# IMU.net
KiCad netlist of a schematic drawn in Altium Designer
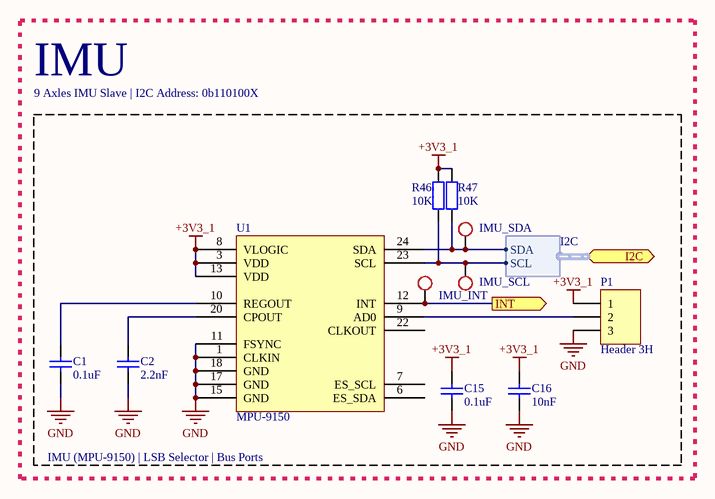
[diagram p0: IMU.SchDoc]

(export (version "E")
  (design (tool "Eeschema 10.0.6"))
  (components
    (comp (ref "C1")
      (value "0.1uF")
      (footprint "C0805")
      (description "Capacitor (Semiconductor SIM Model)")
      (fields (field (name "PUBLISHER") "Altium Limited"))
      (libsource (lib "Miscellaneous Devices") (part "Cap Semi"))
    )
    (comp (ref "C2")
      (value "2.2nF")
      (footprint "C0805")
      (description "Capacitor (Semiconductor SIM Model)")
      (fields (field (name "PUBLISHER") "Altium Limited"))
      (libsource (lib "Miscellaneous Devices") (part "Cap Semi"))
    )
    (comp (ref "C15")
      (value "0.1uF")
      (footprint "C0805")
      (description "Capacitor (Semiconductor SIM Model)")
      (fields (field (name "PUBLISHER") "Altium Limited"))
      (libsource (lib "Miscellaneous Devices") (part "Cap Semi"))
    )
    (comp (ref "C16")
      (value "10nF")
      (footprint "C0805")
      (description "Capacitor (Semiconductor SIM Model)")
      (fields (field (name "PUBLISHER") "Altium Limited"))
      (libsource (lib "Miscellaneous Devices") (part "Cap Semi"))
    )
    (comp (ref "IMU_INT")
      (value "Test Point")
      (footprint "TP1")
      (description "Test Point for Osciloscope measurements")
      (libsource (lib "CustomLibrary") (part "Test Point"))
    )
    (comp (ref "IMU_SCL")
      (value "Test Point")
      (footprint "TP1")
      (description "Test Point for Osciloscope measurements")
      (libsource (lib "CustomLibrary") (part "Test Point"))
    )
    (comp (ref "IMU_SDA")
      (value "Test Point")
      (footprint "TP1")
      (description "Test Point for Osciloscope measurements")
      (libsource (lib "CustomLibrary") (part "Test Point"))
    )
    (comp (ref "P1")
      (value "Header 3H")
      (footprint "HDR1X3H")
      (description "Header, 3-Pin, Right Angle")
      (fields (field (name "PUBLISHER") "Altium Limited"))
      (libsource (lib "Miscellaneous Connectors") (part "Header 3H"))
    )
    (comp (ref "R46") (value "10K") (footprint "RES1206") (libsource (lib "CustomLibrary") (part "RES")))
    (comp (ref "R47") (value "10K") (footprint "RES1206") (libsource (lib "CustomLibrary") (part "RES")))
    (comp (ref "U1")
      (value "MPU-9150")
      (footprint "QFN50P400X400X100-24N")
      (description "InveSense MPU-9150 IMU 9 axles")
      (libsource (lib "CustomLibrary") (part "MPU-9150"))
    )
  )
  (nets
    (net (code "2") (name "+3V3_1") (class "Default")
      (node (ref "C15") (pin "2") (pinfunction "2_2") (pintype "passive"))
      (node (ref "C16") (pin "2") (pinfunction "2_2") (pintype "passive"))
      (node (ref "P1") (pin "1") (pinfunction "1_1") (pintype "passive"))
      (node (ref "R46") (pin "1") (pinfunction "1_1") (pintype "passive"))
      (node (ref "R47") (pin "1") (pinfunction "1_1") (pintype "passive"))
      (node (ref "U1") (pin "13") (pinfunction "VDD_13") (pintype "power_in"))
      (node (ref "U1") (pin "3") (pinfunction "VDD_3") (pintype "power_in"))
      (node (ref "U1") (pin "8") (pinfunction "VLOGIC_8") (pintype "power_in"))
    )
    (net (code "3") (name "/INT") (class "Default")
      (node (ref "IMU_INT") (pin "1") (pinfunction "1_1") (pintype "passive"))
      (node (ref "U1") (pin "12") (pinfunction "INT_12") (pintype "passive"))
    )
    (net (code "5") (name "GND") (class "Default")
      (node (ref "C1") (pin "1") (pinfunction "1_1") (pintype "passive"))
      (node (ref "C15") (pin "1") (pinfunction "1_1") (pintype "passive"))
      (node (ref "C16") (pin "1") (pinfunction "1_1") (pintype "passive"))
      (node (ref "C2") (pin "1") (pinfunction "1_1") (pintype "passive"))
      (node (ref "P1") (pin "3") (pinfunction "3_3") (pintype "passive"))
      (node (ref "U1") (pin "1") (pinfunction "CLKIN_1") (pintype "passive"))
      (node (ref "U1") (pin "11") (pinfunction "FSYNC_11") (pintype "passive"))
      (node (ref "U1") (pin "15") (pinfunction "GND_15") (pintype "power_in"))
      (node (ref "U1") (pin "17") (pinfunction "GND_17") (pintype "power_in"))
      (node (ref "U1") (pin "18") (pinfunction "GND_18") (pintype "power_in"))
    )
    (net (code "6") (name "Net-(U1-AD0)") (class "Default")
      (node (ref "P1") (pin "2") (pinfunction "2_2") (pintype "passive"))
      (node (ref "U1") (pin "9") (pinfunction "AD0_9") (pintype "passive"))
    )
    (net (code "7") (name "Net-(U1-CPOUT)") (class "Default")
      (node (ref "C2") (pin "2") (pinfunction "2_2") (pintype "passive"))
      (node (ref "U1") (pin "20") (pinfunction "CPOUT_20") (pintype "passive"))
    )
    (net (code "8") (name "Net-(U1-REGOUT)") (class "Default")
      (node (ref "C1") (pin "2") (pinfunction "2_2") (pintype "passive"))
      (node (ref "U1") (pin "10") (pinfunction "REGOUT_10") (pintype "passive"))
    )
    (net (code "9") (name "Net-(U1-SCL)") (class "Default")
      (node (ref "IMU_SCL") (pin "1") (pinfunction "1_1") (pintype "passive"))
      (node (ref "R46") (pin "2") (pinfunction "2_2") (pintype "passive"))
      (node (ref "U1") (pin "23") (pinfunction "SCL_23") (pintype "passive"))
    )
    (net (code "10") (name "Net-(U1-SDA)") (class "Default")
      (node (ref "IMU_SDA") (pin "1") (pinfunction "1_1") (pintype "passive"))
      (node (ref "R47") (pin "2") (pinfunction "2_2") (pintype "passive"))
      (node (ref "U1") (pin "24") (pinfunction "SDA_24") (pintype "passive"))
    )
    (net (code "11") (name "unconnected-(U1-CLKOUT-Pad22)") (class "Default")
      (node (ref "U1") (pin "22") (pinfunction "CLKOUT_22") (pintype "passive"))
    )
    (net (code "12") (name "unconnected-(U1-ES_SCL-Pad7)") (class "Default")
      (node (ref "U1") (pin "7") (pinfunction "ES_SCL_7") (pintype "passive"))
    )
    (net (code "13") (name "unconnected-(U1-ES_SDA-Pad6)") (class "Default")
      (node (ref "U1") (pin "6") (pinfunction "ES_SDA_6") (pintype "passive"))
    )
  )
)
